# RJ45_Sheet.net
KiCad netlist of a schematic drawn in Altium Designer
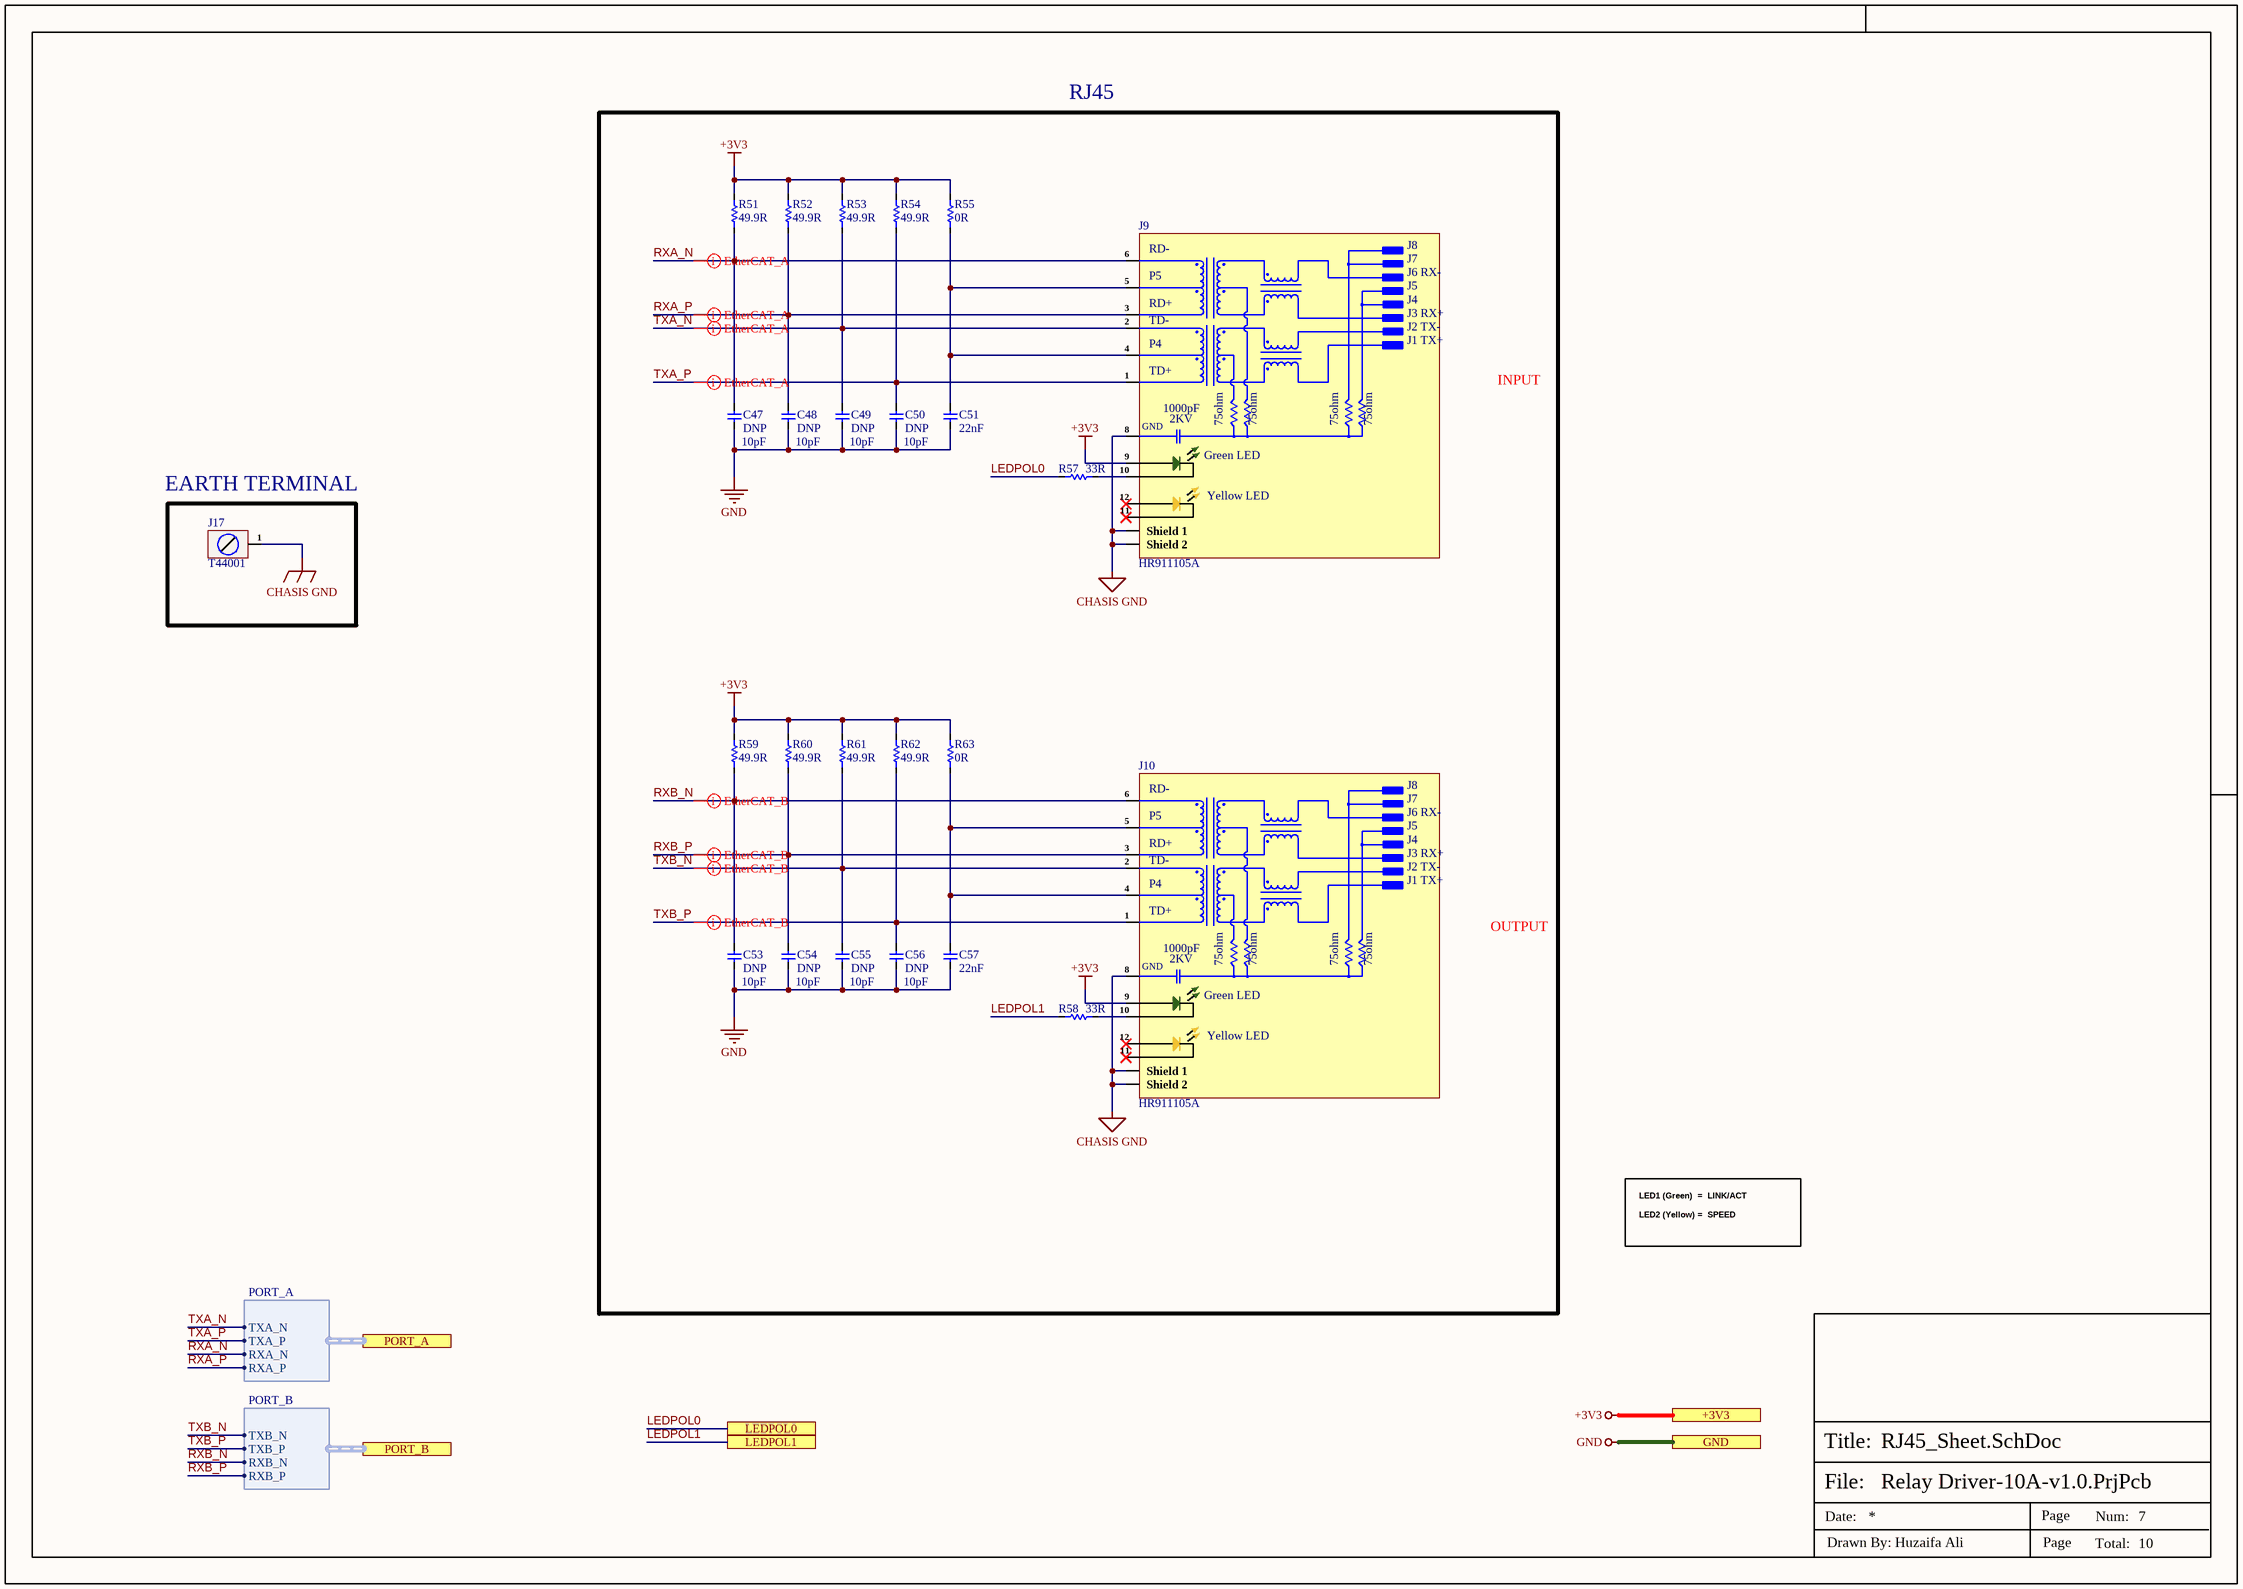
[diagram p0: RJ45_Sheet.SchDoc]

(export (version "E")
  (design (tool "Eeschema 10.0.6"))
  (components
    (comp (ref "C47")
      (value "DNP")
      (footprint "Cap-0402")
      (description "CAP CER 10PF 50V C0G/NP0 0402")
      (fields
        (field (name "MANUFACTURER") "Murata")
        (field (name "MANUFACTURER PART NUMBER") "GRM1555C1H100JA01D")
      )
      (libsource (lib "eSpark Libraries") (part "GRM1555C1H100JA01D"))
    )
    (comp (ref "C48")
      (value "DNP")
      (footprint "Cap-0402")
      (description "CAP CER 10PF 50V C0G/NP0 0402")
      (fields
        (field (name "MANUFACTURER") "Murata")
        (field (name "MANUFACTURER PART NUMBER") "GRM1555C1H100JA01D")
      )
      (libsource (lib "eSpark Libraries") (part "GRM1555C1H100JA01D"))
    )
    (comp (ref "C49")
      (value "DNP")
      (footprint "Cap-0402")
      (description "CAP CER 10PF 50V C0G/NP0 0402")
      (fields
        (field (name "MANUFACTURER") "Murata")
        (field (name "MANUFACTURER PART NUMBER") "GRM1555C1H100JA01D")
      )
      (libsource (lib "eSpark Libraries") (part "GRM1555C1H100JA01D"))
    )
    (comp (ref "C50")
      (value "DNP")
      (footprint "Cap-0402")
      (description "CAP CER 10PF 50V C0G/NP0 0402")
      (fields
        (field (name "MANUFACTURER") "Murata")
        (field (name "MANUFACTURER PART NUMBER") "GRM1555C1H100JA01D")
      )
      (libsource (lib "eSpark Libraries") (part "GRM1555C1H100JA01D"))
    )
    (comp (ref "C51")
      (value "22nF")
      (footprint "Cap-0402")
      (description "CAP CER 0.022UF 16V X7R 0402")
      (fields
        (field (name "MANUFACTURER") "Yageo")
        (field (name "MANUFACTURER PART NUMBER") "CC0402JRX7R7BB223")
      )
      (libsource (lib "eSpark Libraries") (part "CC0402JRX7R7BB223"))
    )
    (comp (ref "C53")
      (value "DNP")
      (footprint "Cap-0402")
      (description "CAP CER 10PF 50V C0G/NP0 0402")
      (fields
        (field (name "MANUFACTURER") "Murata")
        (field (name "MANUFACTURER PART NUMBER") "GRM1555C1H100JA01D")
      )
      (libsource (lib "eSpark Libraries") (part "GRM1555C1H100JA01D"))
    )
    (comp (ref "C54")
      (value "DNP")
      (footprint "Cap-0402")
      (description "CAP CER 10PF 50V C0G/NP0 0402")
      (fields
        (field (name "MANUFACTURER") "Murata")
        (field (name "MANUFACTURER PART NUMBER") "GRM1555C1H100JA01D")
      )
      (libsource (lib "eSpark Libraries") (part "GRM1555C1H100JA01D"))
    )
    (comp (ref "C55")
      (value "DNP")
      (footprint "Cap-0402")
      (description "CAP CER 10PF 50V C0G/NP0 0402")
      (fields
        (field (name "MANUFACTURER") "Murata")
        (field (name "MANUFACTURER PART NUMBER") "GRM1555C1H100JA01D")
      )
      (libsource (lib "eSpark Libraries") (part "GRM1555C1H100JA01D"))
    )
    (comp (ref "C56")
      (value "DNP")
      (footprint "Cap-0402")
      (description "CAP CER 10PF 50V C0G/NP0 0402")
      (fields
        (field (name "MANUFACTURER") "Murata")
        (field (name "MANUFACTURER PART NUMBER") "GRM1555C1H100JA01D")
      )
      (libsource (lib "eSpark Libraries") (part "GRM1555C1H100JA01D"))
    )
    (comp (ref "C57")
      (value "22nF")
      (footprint "Cap-0402")
      (description "CAP CER 0.022UF 16V X7R 0402")
      (fields
        (field (name "MANUFACTURER") "Yageo")
        (field (name "MANUFACTURER PART NUMBER") "CC0402JRX7R7BB223")
      )
      (libsource (lib "eSpark Libraries") (part "CC0402JRX7R7BB223"))
    )
    (comp (ref "J9")
      (value "HR911105A")
      (footprint "HR911105A")
      (description "RJ45 RJReceptacle 1 WithLED Plugin Ethernet Connectors/Modular Connectors (RJ45 RJ11) ROHS")
      (fields (field (name "MANUFACTURER") "HANRUN") (field (name "LCSC PART NUMBER") "C12074"))
      (libsource (lib "eSpark Libraries") (part "HR911105A"))
    )
    (comp (ref "J10")
      (value "HR911105A")
      (footprint "HR911105A")
      (description "RJ45 RJReceptacle 1 WithLED Plugin Ethernet Connectors/Modular Connectors (RJ45 RJ11) ROHS")
      (fields (field (name "MANUFACTURER") "HANRUN") (field (name "LCSC PART NUMBER") "C12074"))
      (libsource (lib "eSpark Libraries") (part "HR911105A"))
    )
    (comp (ref "J17")
      (value "T44001")
      (footprint "T44001")
      (description "M4 Plugin PCB Welding Terminal ROHS")
      (fields (field (name "MANUFACTURER") "XFCN"))
      (libsource (lib "eSpark Libraries") (part "T44001"))
    )
    (comp (ref "R51")
      (value "49.9R")
      (footprint "Res-0603")
      (description "RES 49.9 OHM 1% 1/10W 0603")
      (fields
        (field (name "MANUFACTURER") "Yageo")
        (field (name "MANUFACTURER PART NUMBER") "RC0603FR-0749R9L")
      )
      (libsource (lib "eSpark Libraries") (part "RC0603FR-0749R9L"))
    )
    (comp (ref "R52")
      (value "49.9R")
      (footprint "Res-0603")
      (description "RES 49.9 OHM 1% 1/10W 0603")
      (fields
        (field (name "MANUFACTURER") "Yageo")
        (field (name "MANUFACTURER PART NUMBER") "RC0603FR-0749R9L")
      )
      (libsource (lib "eSpark Libraries") (part "RC0603FR-0749R9L"))
    )
    (comp (ref "R53")
      (value "49.9R")
      (footprint "Res-0603")
      (description "RES 49.9 OHM 1% 1/10W 0603")
      (fields
        (field (name "MANUFACTURER") "Yageo")
        (field (name "MANUFACTURER PART NUMBER") "RC0603FR-0749R9L")
      )
      (libsource (lib "eSpark Libraries") (part "RC0603FR-0749R9L"))
    )
    (comp (ref "R54")
      (value "49.9R")
      (footprint "Res-0603")
      (description "RES 49.9 OHM 1% 1/10W 0603")
      (fields
        (field (name "MANUFACTURER") "Yageo")
        (field (name "MANUFACTURER PART NUMBER") "RC0603FR-0749R9L")
      )
      (libsource (lib "eSpark Libraries") (part "RC0603FR-0749R9L"))
    )
    (comp (ref "R55")
      (value "0R")
      (footprint "Res-0402")
      (description "RESISTOR 0402 JUMPER ZERO OHM")
      (fields
        (field (name "MANUFACTURER") "Yageo")
        (field (name "MANUFACTURER PART NUMBER") "AC0402FR-070RL")
      )
      (libsource (lib "eSpark Libraries") (part "AC0402FR-070RL"))
    )
    (comp (ref "R57")
      (value "33R")
      (footprint "Res-0402")
      (description "RES 33 OHM 1% 1/16W 0402")
      (fields
        (field (name "MANUFACTURER") "Yageo")
        (field (name "MANUFACTURER PART NUMBER") "RC0402FR-0733RL")
      )
      (libsource (lib "eSpark Libraries") (part "RC0402FR-0733RL"))
    )
    (comp (ref "R58")
      (value "33R")
      (footprint "Res-0402")
      (description "RES 33 OHM 1% 1/16W 0402")
      (fields
        (field (name "MANUFACTURER") "Yageo")
        (field (name "MANUFACTURER PART NUMBER") "RC0402FR-0733RL")
      )
      (libsource (lib "eSpark Libraries") (part "RC0402FR-0733RL"))
    )
    (comp (ref "R59")
      (value "49.9R")
      (footprint "Res-0603")
      (description "RES 49.9 OHM 1% 1/10W 0603")
      (fields
        (field (name "MANUFACTURER") "Yageo")
        (field (name "MANUFACTURER PART NUMBER") "RC0603FR-0749R9L")
      )
      (libsource (lib "eSpark Libraries") (part "RC0603FR-0749R9L"))
    )
    (comp (ref "R60")
      (value "49.9R")
      (footprint "Res-0603")
      (description "RES 49.9 OHM 1% 1/10W 0603")
      (fields
        (field (name "MANUFACTURER") "Yageo")
        (field (name "MANUFACTURER PART NUMBER") "RC0603FR-0749R9L")
      )
      (libsource (lib "eSpark Libraries") (part "RC0603FR-0749R9L"))
    )
    (comp (ref "R61")
      (value "49.9R")
      (footprint "Res-0603")
      (description "RES 49.9 OHM 1% 1/10W 0603")
      (fields
        (field (name "MANUFACTURER") "Yageo")
        (field (name "MANUFACTURER PART NUMBER") "RC0603FR-0749R9L")
      )
      (libsource (lib "eSpark Libraries") (part "RC0603FR-0749R9L"))
    )
    (comp (ref "R62")
      (value "49.9R")
      (footprint "Res-0603")
      (description "RES 49.9 OHM 1% 1/10W 0603")
      (fields
        (field (name "MANUFACTURER") "Yageo")
        (field (name "MANUFACTURER PART NUMBER") "RC0603FR-0749R9L")
      )
      (libsource (lib "eSpark Libraries") (part "RC0603FR-0749R9L"))
    )
    (comp (ref "R63")
      (value "0R")
      (footprint "Res-0402")
      (description "RESISTOR 0402 JUMPER ZERO OHM")
      (fields
        (field (name "MANUFACTURER") "Yageo")
        (field (name "MANUFACTURER PART NUMBER") "AC0402FR-070RL")
      )
      (libsource (lib "eSpark Libraries") (part "AC0402FR-070RL"))
    )
  )
  (nets
    (net (code "3") (name "+3V3") (class "Default")
      (node (ref "J10") (pin "9") (pinfunction "ANODE_9") (pintype "passive"))
      (node (ref "J9") (pin "9") (pinfunction "ANODE_9") (pintype "passive"))
      (node (ref "R51") (pin "2") (pinfunction "2_2") (pintype "passive"))
      (node (ref "R52") (pin "2") (pinfunction "2_2") (pintype "passive"))
      (node (ref "R53") (pin "2") (pinfunction "2_2") (pintype "passive"))
      (node (ref "R54") (pin "2") (pinfunction "2_2") (pintype "passive"))
      (node (ref "R55") (pin "2") (pinfunction "2_2") (pintype "passive"))
      (node (ref "R59") (pin "2") (pinfunction "2_2") (pintype "passive"))
      (node (ref "R60") (pin "2") (pinfunction "2_2") (pintype "passive"))
      (node (ref "R61") (pin "2") (pinfunction "2_2") (pintype "passive"))
      (node (ref "R62") (pin "2") (pinfunction "2_2") (pintype "passive"))
      (node (ref "R63") (pin "2") (pinfunction "2_2") (pintype "passive"))
    )
    (net (code "4") (name "/LEDPOL0") (class "Default")
      (node (ref "R57") (pin "1") (pinfunction "1_1") (pintype "passive"))
    )
    (net (code "5") (name "/LEDPOL1") (class "Default")
      (node (ref "R58") (pin "1") (pinfunction "1_1") (pintype "passive"))
    )
    (net (code "6") (name "/RXA_N") (class "Default")
      (node (ref "C47") (pin "2") (pinfunction "2_2") (pintype "passive"))
      (node (ref "J9") (pin "6") (pinfunction "RD-_6") (pintype "passive"))
      (node (ref "R51") (pin "1") (pinfunction "1_1") (pintype "passive"))
    )
    (net (code "7") (name "/RXA_P") (class "Default")
      (node (ref "C48") (pin "2") (pinfunction "2_2") (pintype "passive"))
      (node (ref "J9") (pin "3") (pinfunction "RD+_3") (pintype "passive"))
      (node (ref "R52") (pin "1") (pinfunction "1_1") (pintype "passive"))
    )
    (net (code "8") (name "/RXB_N") (class "Default")
      (node (ref "C53") (pin "2") (pinfunction "2_2") (pintype "passive"))
      (node (ref "J10") (pin "6") (pinfunction "RD-_6") (pintype "passive"))
      (node (ref "R59") (pin "1") (pinfunction "1_1") (pintype "passive"))
    )
    (net (code "9") (name "/RXB_P") (class "Default")
      (node (ref "C54") (pin "2") (pinfunction "2_2") (pintype "passive"))
      (node (ref "J10") (pin "3") (pinfunction "RD+_3") (pintype "passive"))
      (node (ref "R60") (pin "1") (pinfunction "1_1") (pintype "passive"))
    )
    (net (code "10") (name "/TXA_N") (class "Default")
      (node (ref "C49") (pin "2") (pinfunction "2_2") (pintype "passive"))
      (node (ref "J9") (pin "2") (pinfunction "TD-_2") (pintype "passive"))
      (node (ref "R53") (pin "1") (pinfunction "1_1") (pintype "passive"))
    )
    (net (code "11") (name "/TXA_P") (class "Default")
      (node (ref "C50") (pin "2") (pinfunction "2_2") (pintype "passive"))
      (node (ref "J9") (pin "1") (pinfunction "TD+_1") (pintype "passive"))
      (node (ref "R54") (pin "1") (pinfunction "1_1") (pintype "passive"))
    )
    (net (code "12") (name "/TXB_N") (class "Default")
      (node (ref "C55") (pin "2") (pinfunction "2_2") (pintype "passive"))
      (node (ref "J10") (pin "2") (pinfunction "TD-_2") (pintype "passive"))
      (node (ref "R61") (pin "1") (pinfunction "1_1") (pintype "passive"))
    )
    (net (code "13") (name "/TXB_P") (class "Default")
      (node (ref "C56") (pin "2") (pinfunction "2_2") (pintype "passive"))
      (node (ref "J10") (pin "1") (pinfunction "TD+_1") (pintype "passive"))
      (node (ref "R62") (pin "1") (pinfunction "1_1") (pintype "passive"))
    )
    (net (code "16") (name "CHASIS GND") (class "Default")
      (node (ref "J10") (pin "8") (pinfunction "GND_8") (pintype "power_in"))
      (node (ref "J10") (pin "Shield_1") (pinfunction "Shield_1_Shield_1") (pintype "passive"))
      (node (ref "J10") (pin "Shield_2") (pinfunction "Shield_2_Shield_2") (pintype "passive"))
      (node (ref "J17") (pin "1") (pinfunction "1_1") (pintype "passive"))
      (node (ref "J9") (pin "8") (pinfunction "GND_8") (pintype "power_in"))
      (node (ref "J9") (pin "Shield_1") (pinfunction "Shield_1_Shield_1") (pintype "passive"))
      (node (ref "J9") (pin "Shield_2") (pinfunction "Shield_2_Shield_2") (pintype "passive"))
    )
    (net (code "17") (name "GND") (class "Default")
      (node (ref "C47") (pin "1") (pinfunction "1_1") (pintype "passive"))
      (node (ref "C48") (pin "1") (pinfunction "1_1") (pintype "passive"))
      (node (ref "C49") (pin "1") (pinfunction "1_1") (pintype "passive"))
      (node (ref "C50") (pin "1") (pinfunction "1_1") (pintype "passive"))
      (node (ref "C51") (pin "1") (pinfunction "1_1") (pintype "passive"))
      (node (ref "C53") (pin "1") (pinfunction "1_1") (pintype "passive"))
      (node (ref "C54") (pin "1") (pinfunction "1_1") (pintype "passive"))
      (node (ref "C55") (pin "1") (pinfunction "1_1") (pintype "passive"))
      (node (ref "C56") (pin "1") (pinfunction "1_1") (pintype "passive"))
      (node (ref "C57") (pin "1") (pinfunction "1_1") (pintype "passive"))
    )
    (net (code "18") (name "Net-(J9-CATHODE-Pad10)") (class "Default")
      (node (ref "J9") (pin "10") (pinfunction "CATHODE_10") (pintype "passive"))
      (node (ref "R57") (pin "2") (pinfunction "2_2") (pintype "passive"))
    )
    (net (code "19") (name "Net-(J9-P4)") (class "Default")
      (node (ref "C51") (pin "2") (pinfunction "2_2") (pintype "passive"))
      (node (ref "J9") (pin "4") (pinfunction "P4_4") (pintype "passive"))
      (node (ref "J9") (pin "5") (pinfunction "P5_5") (pintype "passive"))
      (node (ref "R55") (pin "1") (pinfunction "1_1") (pintype "passive"))
    )
    (net (code "20") (name "Net-(J10-CATHODE-Pad10)") (class "Default")
      (node (ref "J10") (pin "10") (pinfunction "CATHODE_10") (pintype "passive"))
      (node (ref "R58") (pin "2") (pinfunction "2_2") (pintype "passive"))
    )
    (net (code "21") (name "Net-(J10-P4)") (class "Default")
      (node (ref "C57") (pin "2") (pinfunction "2_2") (pintype "passive"))
      (node (ref "J10") (pin "4") (pinfunction "P4_4") (pintype "passive"))
      (node (ref "J10") (pin "5") (pinfunction "P5_5") (pintype "passive"))
      (node (ref "R63") (pin "1") (pinfunction "1_1") (pintype "passive"))
    )
    (net (code "22") (name "unconnected-(J9-ANODE-Pad12)") (class "Default")
      (node (ref "J9") (pin "12") (pinfunction "ANODE_12") (pintype "passive+no_connect"))
    )
    (net (code "23") (name "unconnected-(J9-CATHODE-Pad11)") (class "Default")
      (node (ref "J9") (pin "11") (pinfunction "CATHODE_11") (pintype "passive+no_connect"))
    )
    (net (code "24") (name "unconnected-(J10-ANODE-Pad12)") (class "Default")
      (node (ref "J10") (pin "12") (pinfunction "ANODE_12") (pintype "passive+no_connect"))
    )
    (net (code "25") (name "unconnected-(J10-CATHODE-Pad11)") (class "Default")
      (node (ref "J10") (pin "11") (pinfunction "CATHODE_11") (pintype "passive+no_connect"))
    )
  )
)
